# MCU_EGT.net
KiCad netlist of a schematic drawn in Altium Designer
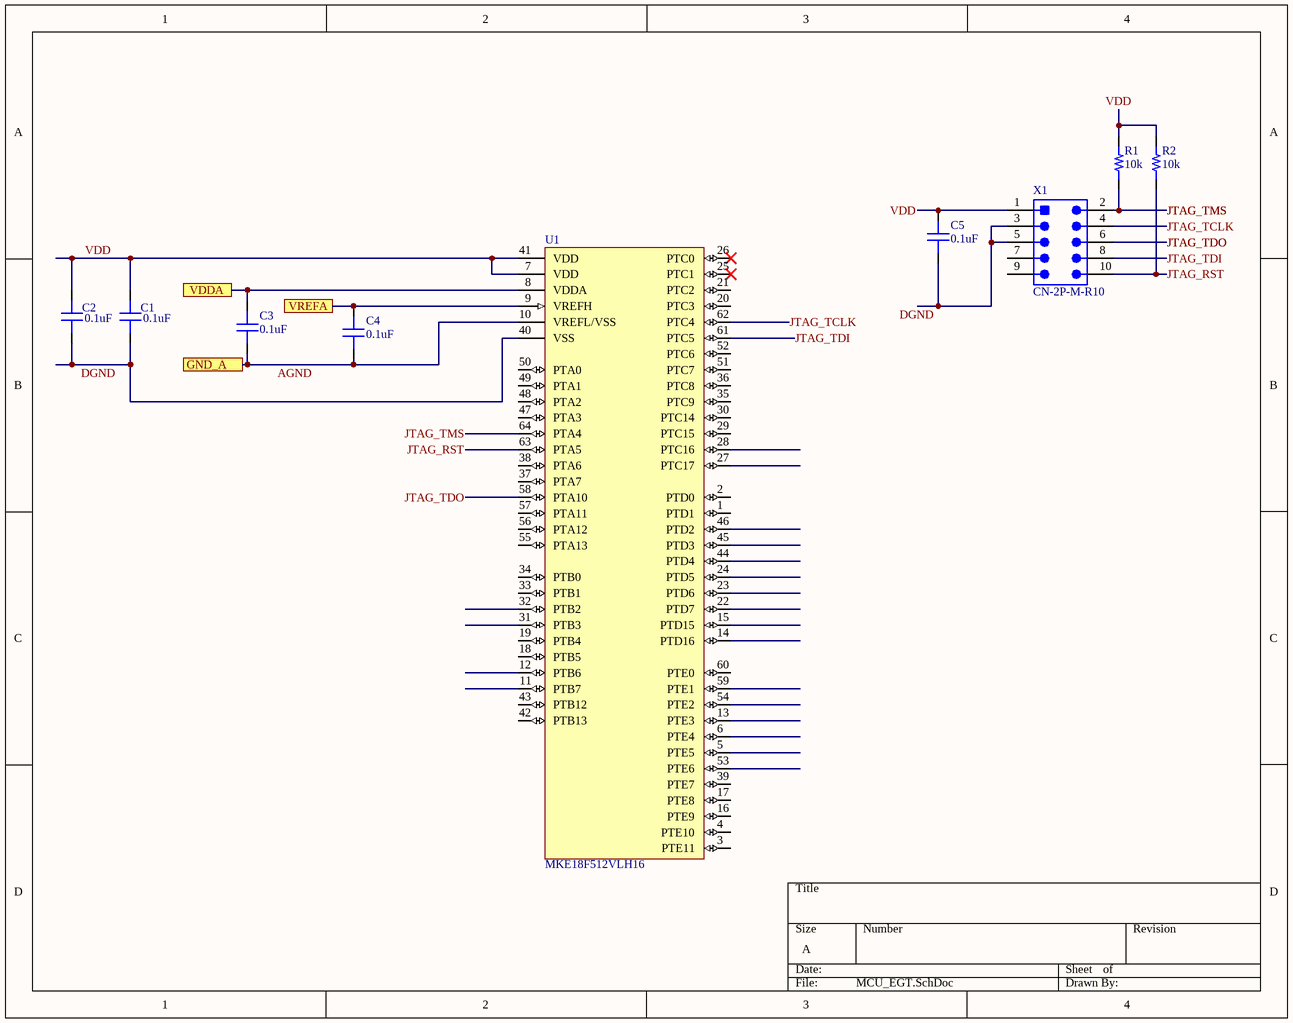
[diagram p0: MCU_EGT.SchDoc]

(export (version "E")
  (design (tool "Eeschema 10.0.6"))
  (components
    (comp (ref "C1")
      (value "capacitor")
      (footprint "0603")
      (description "Generic 0603 capacitor")
      (fields (field (name "CAPACITANCE") "0.1uF") (field (name "VOLTAGE") "50"))
      (libsource (lib "altlib") (part "capacitor"))
    )
    (comp (ref "C2")
      (value "capacitor")
      (footprint "0603")
      (description "Generic 0603 capacitor")
      (fields (field (name "CAPACITANCE") "0.1uF") (field (name "VOLTAGE") "50"))
      (libsource (lib "altlib") (part "capacitor"))
    )
    (comp (ref "C3")
      (value "capacitor")
      (footprint "0603")
      (description "Generic 0603 capacitor")
      (fields (field (name "CAPACITANCE") "0.1uF") (field (name "VOLTAGE") "50"))
      (libsource (lib "altlib") (part "capacitor"))
    )
    (comp (ref "C4")
      (value "capacitor")
      (footprint "0603")
      (description "Generic 0603 capacitor")
      (fields (field (name "CAPACITANCE") "0.1uF") (field (name "VOLTAGE") "50"))
      (libsource (lib "altlib") (part "capacitor"))
    )
    (comp (ref "C5")
      (value "capacitor")
      (footprint "0603")
      (description "Generic 0603 capacitor")
      (fields (field (name "CAPACITANCE") "0.1uF") (field (name "VOLTAGE") "50"))
      (libsource (lib "altlib") (part "capacitor"))
    )
    (comp (ref "R1")
      (value "resistor")
      (footprint "0603")
      (fields (field (name "RESISTANCE") "10k"))
      (libsource (lib "altlib") (part "resistor"))
    )
    (comp (ref "R2")
      (value "resistor")
      (footprint "0603")
      (fields (field (name "RESISTANCE") "10k"))
      (libsource (lib "altlib") (part "resistor"))
    )
    (comp (ref "U1")
      (value "MKE18F512VLH16")
      (footprint "TQFP64")
      (description "32b NXP Microcontroller")
      (libsource (lib "altlib") (part "MKE18F512VLH16"))
    )
    (comp (ref "X1")
      (value "CN-2P-M-R10")
      (footprint "HDR2X5_SMT")
      (description "CONN_TE_2X5POS")
      (libsource (lib "altlib") (part "CN-2P-M-R10"))
    )
  )
  (nets
    (net (code "1") (name "/AGND") (class "Default")
      (node (ref "C3") (pin "1") (pinfunction "1_1") (pintype "passive"))
      (node (ref "C4") (pin "1") (pinfunction "1_1") (pintype "passive"))
      (node (ref "U1") (pin "10") (pinfunction "VREFL/VSS_10") (pintype "power_in"))
    )
    (net (code "2") (name "/DGND") (class "Default")
      (node (ref "C1") (pin "1") (pinfunction "1_1") (pintype "passive"))
      (node (ref "C2") (pin "1") (pinfunction "1_1") (pintype "passive"))
      (node (ref "C5") (pin "1") (pinfunction "1_1") (pintype "passive"))
      (node (ref "U1") (pin "40") (pinfunction "VSS_40") (pintype "power_in"))
      (node (ref "X1") (pin "3") (pinfunction "3_3") (pintype "passive"))
      (node (ref "X1") (pin "5") (pinfunction "5_5") (pintype "passive"))
    )
    (net (code "3") (name "/JTAG_RST") (class "Default")
      (node (ref "R2") (pin "1") (pinfunction "1_1") (pintype "passive"))
      (node (ref "U1") (pin "63") (pinfunction "PTA5_63") (pintype "bidirectional"))
      (node (ref "X1") (pin "10") (pinfunction "10_10") (pintype "passive"))
    )
    (net (code "4") (name "/JTAG_TCLK") (class "Default")
      (node (ref "U1") (pin "62") (pinfunction "PTC4_62") (pintype "bidirectional"))
      (node (ref "X1") (pin "4") (pinfunction "4_4") (pintype "passive"))
    )
    (net (code "5") (name "/JTAG_TDI") (class "Default")
      (node (ref "U1") (pin "61") (pinfunction "PTC5_61") (pintype "bidirectional"))
      (node (ref "X1") (pin "8") (pinfunction "8_8") (pintype "passive"))
    )
    (net (code "6") (name "/JTAG_TDO") (class "Default")
      (node (ref "U1") (pin "58") (pinfunction "PTA10_58") (pintype "bidirectional"))
      (node (ref "X1") (pin "6") (pinfunction "6_6") (pintype "passive"))
    )
    (net (code "7") (name "/JTAG_TMS") (class "Default")
      (node (ref "R1") (pin "1") (pinfunction "1_1") (pintype "passive"))
      (node (ref "U1") (pin "64") (pinfunction "PTA4_64") (pintype "bidirectional"))
      (node (ref "X1") (pin "2") (pinfunction "2_2") (pintype "passive"))
    )
    (net (code "8") (name "/VDD") (class "Default")
      (node (ref "C1") (pin "2") (pinfunction "2_2") (pintype "passive"))
      (node (ref "C2") (pin "2") (pinfunction "2_2") (pintype "passive"))
      (node (ref "C5") (pin "2") (pinfunction "2_2") (pintype "passive"))
      (node (ref "R1") (pin "2") (pinfunction "2_2") (pintype "passive"))
      (node (ref "R2") (pin "2") (pinfunction "2_2") (pintype "passive"))
      (node (ref "U1") (pin "41") (pinfunction "VDD_41") (pintype "power_in"))
      (node (ref "U1") (pin "7") (pinfunction "VDD_7") (pintype "power_in"))
      (node (ref "X1") (pin "1") (pinfunction "1_1") (pintype "passive"))
    )
    (net (code "9") (name "/VDDA") (class "Default")
      (node (ref "C3") (pin "2") (pinfunction "2_2") (pintype "passive"))
      (node (ref "U1") (pin "8") (pinfunction "VDDA_8") (pintype "power_in"))
    )
    (net (code "10") (name "/VREFA") (class "Default")
      (node (ref "C4") (pin "2") (pinfunction "2_2") (pintype "passive"))
      (node (ref "U1") (pin "9") (pinfunction "VREFH_9") (pintype "input"))
    )
    (net (code "11") (name "unconnected-(U1-PTA0-Pad50)") (class "Default")
      (node (ref "U1") (pin "50") (pinfunction "PTA0_50") (pintype "bidirectional"))
    )
    (net (code "12") (name "unconnected-(U1-PTA1-Pad49)") (class "Default")
      (node (ref "U1") (pin "49") (pinfunction "PTA1_49") (pintype "bidirectional"))
    )
    (net (code "13") (name "unconnected-(U1-PTA2-Pad48)") (class "Default")
      (node (ref "U1") (pin "48") (pinfunction "PTA2_48") (pintype "bidirectional"))
    )
    (net (code "14") (name "unconnected-(U1-PTA3-Pad47)") (class "Default")
      (node (ref "U1") (pin "47") (pinfunction "PTA3_47") (pintype "bidirectional"))
    )
    (net (code "15") (name "unconnected-(U1-PTA6-Pad38)") (class "Default")
      (node (ref "U1") (pin "38") (pinfunction "PTA6_38") (pintype "bidirectional"))
    )
    (net (code "16") (name "unconnected-(U1-PTA7-Pad37)") (class "Default")
      (node (ref "U1") (pin "37") (pinfunction "PTA7_37") (pintype "bidirectional"))
    )
    (net (code "17") (name "unconnected-(U1-PTA11-Pad57)") (class "Default")
      (node (ref "U1") (pin "57") (pinfunction "PTA11_57") (pintype "bidirectional"))
    )
    (net (code "18") (name "unconnected-(U1-PTA12-Pad56)") (class "Default")
      (node (ref "U1") (pin "56") (pinfunction "PTA12_56") (pintype "bidirectional"))
    )
    (net (code "19") (name "unconnected-(U1-PTA13-Pad55)") (class "Default")
      (node (ref "U1") (pin "55") (pinfunction "PTA13_55") (pintype "bidirectional"))
    )
    (net (code "20") (name "unconnected-(U1-PTB0-Pad34)") (class "Default")
      (node (ref "U1") (pin "34") (pinfunction "PTB0_34") (pintype "bidirectional"))
    )
    (net (code "21") (name "unconnected-(U1-PTB1-Pad33)") (class "Default")
      (node (ref "U1") (pin "33") (pinfunction "PTB1_33") (pintype "bidirectional"))
    )
    (net (code "22") (name "unconnected-(U1-PTB2-Pad32)") (class "Default")
      (node (ref "U1") (pin "32") (pinfunction "PTB2_32") (pintype "bidirectional"))
    )
    (net (code "23") (name "unconnected-(U1-PTB3-Pad31)") (class "Default")
      (node (ref "U1") (pin "31") (pinfunction "PTB3_31") (pintype "bidirectional"))
    )
    (net (code "24") (name "unconnected-(U1-PTB4-Pad19)") (class "Default")
      (node (ref "U1") (pin "19") (pinfunction "PTB4_19") (pintype "bidirectional"))
    )
    (net (code "25") (name "unconnected-(U1-PTB5-Pad18)") (class "Default")
      (node (ref "U1") (pin "18") (pinfunction "PTB5_18") (pintype "bidirectional"))
    )
    (net (code "26") (name "unconnected-(U1-PTB6-Pad12)") (class "Default")
      (node (ref "U1") (pin "12") (pinfunction "PTB6_12") (pintype "bidirectional"))
    )
    (net (code "27") (name "unconnected-(U1-PTB7-Pad11)") (class "Default")
      (node (ref "U1") (pin "11") (pinfunction "PTB7_11") (pintype "bidirectional"))
    )
    (net (code "28") (name "unconnected-(U1-PTB12-Pad43)") (class "Default")
      (node (ref "U1") (pin "43") (pinfunction "PTB12_43") (pintype "bidirectional"))
    )
    (net (code "29") (name "unconnected-(U1-PTB13-Pad42)") (class "Default")
      (node (ref "U1") (pin "42") (pinfunction "PTB13_42") (pintype "bidirectional"))
    )
    (net (code "30") (name "unconnected-(U1-PTC0-Pad26)") (class "Default")
      (node (ref "U1") (pin "26") (pinfunction "PTC0_26") (pintype "bidirectional+no_connect"))
    )
    (net (code "31") (name "unconnected-(U1-PTC1-Pad25)") (class "Default")
      (node (ref "U1") (pin "25") (pinfunction "PTC1_25") (pintype "bidirectional+no_connect"))
    )
    (net (code "32") (name "unconnected-(U1-PTC2-Pad21)") (class "Default")
      (node (ref "U1") (pin "21") (pinfunction "PTC2_21") (pintype "bidirectional"))
    )
    (net (code "33") (name "unconnected-(U1-PTC3-Pad20)") (class "Default")
      (node (ref "U1") (pin "20") (pinfunction "PTC3_20") (pintype "bidirectional"))
    )
    (net (code "34") (name "unconnected-(U1-PTC6-Pad52)") (class "Default")
      (node (ref "U1") (pin "52") (pinfunction "PTC6_52") (pintype "bidirectional"))
    )
    (net (code "35") (name "unconnected-(U1-PTC7-Pad51)") (class "Default")
      (node (ref "U1") (pin "51") (pinfunction "PTC7_51") (pintype "bidirectional"))
    )
    (net (code "36") (name "unconnected-(U1-PTC8-Pad36)") (class "Default")
      (node (ref "U1") (pin "36") (pinfunction "PTC8_36") (pintype "bidirectional"))
    )
    (net (code "37") (name "unconnected-(U1-PTC9-Pad35)") (class "Default")
      (node (ref "U1") (pin "35") (pinfunction "PTC9_35") (pintype "bidirectional"))
    )
    (net (code "38") (name "unconnected-(U1-PTC14-Pad30)") (class "Default")
      (node (ref "U1") (pin "30") (pinfunction "PTC14_30") (pintype "bidirectional"))
    )
    (net (code "39") (name "unconnected-(U1-PTC15-Pad29)") (class "Default")
      (node (ref "U1") (pin "29") (pinfunction "PTC15_29") (pintype "bidirectional"))
    )
    (net (code "40") (name "unconnected-(U1-PTC16-Pad28)") (class "Default")
      (node (ref "U1") (pin "28") (pinfunction "PTC16_28") (pintype "bidirectional"))
    )
    (net (code "41") (name "unconnected-(U1-PTC17-Pad27)") (class "Default")
      (node (ref "U1") (pin "27") (pinfunction "PTC17_27") (pintype "bidirectional"))
    )
    (net (code "42") (name "unconnected-(U1-PTD0-Pad2)") (class "Default")
      (node (ref "U1") (pin "2") (pinfunction "PTD0_2") (pintype "bidirectional"))
    )
    (net (code "43") (name "unconnected-(U1-PTD1-Pad1)") (class "Default")
      (node (ref "U1") (pin "1") (pinfunction "PTD1_1") (pintype "bidirectional"))
    )
    (net (code "44") (name "unconnected-(U1-PTD2-Pad46)") (class "Default")
      (node (ref "U1") (pin "46") (pinfunction "PTD2_46") (pintype "bidirectional"))
    )
    (net (code "45") (name "unconnected-(U1-PTD3-Pad45)") (class "Default")
      (node (ref "U1") (pin "45") (pinfunction "PTD3_45") (pintype "bidirectional"))
    )
    (net (code "46") (name "unconnected-(U1-PTD4-Pad44)") (class "Default")
      (node (ref "U1") (pin "44") (pinfunction "PTD4_44") (pintype "bidirectional"))
    )
    (net (code "47") (name "unconnected-(U1-PTD5-Pad24)") (class "Default")
      (node (ref "U1") (pin "24") (pinfunction "PTD5_24") (pintype "bidirectional"))
    )
    (net (code "48") (name "unconnected-(U1-PTD6-Pad23)") (class "Default")
      (node (ref "U1") (pin "23") (pinfunction "PTD6_23") (pintype "bidirectional"))
    )
    (net (code "49") (name "unconnected-(U1-PTD7-Pad22)") (class "Default")
      (node (ref "U1") (pin "22") (pinfunction "PTD7_22") (pintype "bidirectional"))
    )
    (net (code "50") (name "unconnected-(U1-PTD15-Pad15)") (class "Default")
      (node (ref "U1") (pin "15") (pinfunction "PTD15_15") (pintype "bidirectional"))
    )
    (net (code "51") (name "unconnected-(U1-PTD16-Pad14)") (class "Default")
      (node (ref "U1") (pin "14") (pinfunction "PTD16_14") (pintype "bidirectional"))
    )
    (net (code "52") (name "unconnected-(U1-PTE0-Pad60)") (class "Default")
      (node (ref "U1") (pin "60") (pinfunction "PTE0_60") (pintype "bidirectional"))
    )
    (net (code "53") (name "unconnected-(U1-PTE1-Pad59)") (class "Default")
      (node (ref "U1") (pin "59") (pinfunction "PTE1_59") (pintype "bidirectional"))
    )
    (net (code "54") (name "unconnected-(U1-PTE2-Pad54)") (class "Default")
      (node (ref "U1") (pin "54") (pinfunction "PTE2_54") (pintype "bidirectional"))
    )
    (net (code "55") (name "unconnected-(U1-PTE3-Pad13)") (class "Default")
      (node (ref "U1") (pin "13") (pinfunction "PTE3_13") (pintype "bidirectional"))
    )
    (net (code "56") (name "unconnected-(U1-PTE4-Pad6)") (class "Default")
      (node (ref "U1") (pin "6") (pinfunction "PTE4_6") (pintype "bidirectional"))
    )
    (net (code "57") (name "unconnected-(U1-PTE5-Pad5)") (class "Default")
      (node (ref "U1") (pin "5") (pinfunction "PTE5_5") (pintype "bidirectional"))
    )
    (net (code "58") (name "unconnected-(U1-PTE6-Pad53)") (class "Default")
      (node (ref "U1") (pin "53") (pinfunction "PTE6_53") (pintype "bidirectional"))
    )
    (net (code "59") (name "unconnected-(U1-PTE7-Pad39)") (class "Default")
      (node (ref "U1") (pin "39") (pinfunction "PTE7_39") (pintype "bidirectional"))
    )
    (net (code "60") (name "unconnected-(U1-PTE8-Pad17)") (class "Default")
      (node (ref "U1") (pin "17") (pinfunction "PTE8_17") (pintype "bidirectional"))
    )
    (net (code "61") (name "unconnected-(U1-PTE9-Pad16)") (class "Default")
      (node (ref "U1") (pin "16") (pinfunction "PTE9_16") (pintype "bidirectional"))
    )
    (net (code "62") (name "unconnected-(U1-PTE10-Pad4)") (class "Default")
      (node (ref "U1") (pin "4") (pinfunction "PTE10_4") (pintype "bidirectional"))
    )
    (net (code "63") (name "unconnected-(U1-PTE11-Pad3)") (class "Default")
      (node (ref "U1") (pin "3") (pinfunction "PTE11_3") (pintype "bidirectional"))
    )
    (net (code "64") (name "unconnected-(X1-Pad7)") (class "Default")
      (node (ref "X1") (pin "7") (pinfunction "7_7") (pintype "passive"))
    )
    (net (code "65") (name "unconnected-(X1-Pad9)") (class "Default")
      (node (ref "X1") (pin "9") (pinfunction "9_9") (pintype "passive"))
    )
  )
)
